# schematic-MAX6675.net
KiCad netlist of a schematic drawn in EAGLE
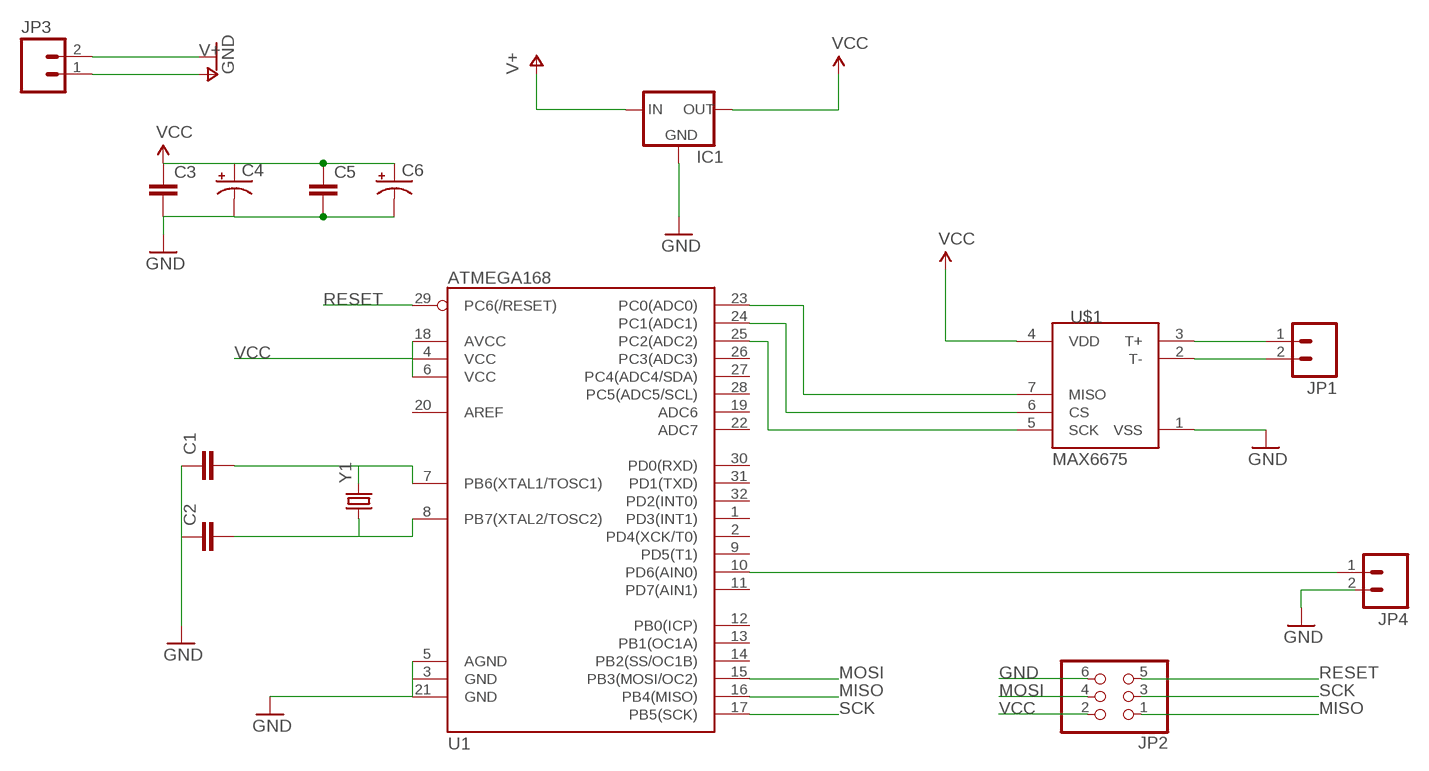
[diagram p0: schematic, sheet 1]

(export (version "E")
  (design (tool "Eeschema 10.0.6"))
  (components
    (comp (ref "C1")
      (value "CAPPTH2")
      (footprint "eagle-import:CAP-PTH-SMALL2")
      (libsource (lib "eagle-import") (part "CAPPTH2"))
    )
    (comp (ref "C2")
      (value "CAPPTH2")
      (footprint "eagle-import:CAP-PTH-SMALL2")
      (libsource (lib "eagle-import") (part "CAPPTH2"))
    )
    (comp (ref "C3")
      (value "CAPPTH")
      (footprint "eagle-import:CAP-PTH-SMALL")
      (libsource (lib "eagle-import") (part "CAPPTH"))
    )
    (comp (ref "C4")
      (value "CAP_POLPTH2")
      (footprint "eagle-import:CPOL-RADIAL-10UF-25V")
      (libsource (lib "eagle-import") (part "CAP_POLPTH2"))
    )
    (comp (ref "C5")
      (value "CAPPTH")
      (footprint "eagle-import:CAP-PTH-SMALL")
      (libsource (lib "eagle-import") (part "CAPPTH"))
    )
    (comp (ref "C6")
      (value "CAP_POLPTH2")
      (footprint "eagle-import:CPOL-RADIAL-10UF-25V")
      (libsource (lib "eagle-import") (part "CAP_POLPTH2"))
    )
    (comp (ref "IC1")
      (value "V_REG_78XXSINK")
      (footprint "eagle-import:TO220-IGO")
      (libsource (lib "eagle-import") (part "V_REG_78XXSINK"))
    )
    (comp (ref "JP1")
      (value "M025MM")
      (footprint "eagle-import:SCREWTERMINAL-5MM-2")
      (libsource (lib "eagle-import") (part "M025MM"))
    )
    (comp (ref "JP2")
      (value "PINHD-2X3")
      (footprint "eagle-import:2X03")
      (libsource (lib "eagle-import") (part "PINHD-2X3"))
    )
    (comp (ref "JP3")
      (value "M023.5MM_LOCK")
      (footprint "eagle-import:SCREWTERMINAL-3.5MM-2_LOCK")
      (libsource (lib "eagle-import") (part "M023.5MM_LOCK"))
    )
    (comp (ref "JP4")
      (value "M023.5MM_LOCK")
      (footprint "eagle-import:SCREWTERMINAL-3.5MM-2_LOCK")
      (libsource (lib "eagle-import") (part "M023.5MM_LOCK"))
    )
    (comp (ref "U$1")
      (value "MAX6675")
      (footprint "eagle-import:SO08-MAX6675")
      (libsource (lib "eagle-import") (part "MAX6675"))
    )
    (comp (ref "U1")
      (value "ATMEGA168")
      (footprint "eagle-import:TQFP32-08")
      (libsource (lib "eagle-import") (part "ATMEGA168"))
    )
    (comp (ref "Y1")
      (value "CRYSTALHC49US")
      (footprint "eagle-import:HC49US")
      (libsource (lib "eagle-import") (part "CRYSTALHC49US"))
    )
  )
  (nets
    (net (code "1") (name "/MISO") (class "Default")
      (node (ref "JP2") (pin "1") (pinfunction "1_1") (pintype "passive"))
      (node (ref "U1") (pin "16") (pinfunction "PB4(MISO)_16") (pintype "bidirectional"))
    )
    (net (code "2") (name "/MOSI") (class "Default")
      (node (ref "JP2") (pin "4") (pinfunction "4_4") (pintype "passive"))
      (node (ref "U1") (pin "15") (pinfunction "PB3(MOSI/OC2)_15") (pintype "bidirectional"))
    )
    (net (code "3") (name "/RESET") (class "Default")
      (node (ref "JP2") (pin "5") (pinfunction "5_5") (pintype "passive"))
      (node (ref "U1") (pin "29") (pinfunction "PC6(/RESET)_29") (pintype "bidirectional"))
    )
    (net (code "4") (name "/SCK") (class "Default")
      (node (ref "JP2") (pin "3") (pinfunction "3_3") (pintype "passive"))
      (node (ref "U1") (pin "17") (pinfunction "PB5(SCK)_17") (pintype "bidirectional"))
    )
    (net (code "5") (name "GND") (class "Default")
      (node (ref "C1") (pin "1") (pinfunction "1_1") (pintype "passive"))
      (node (ref "C2") (pin "1") (pinfunction "1_1") (pintype "passive"))
      (node (ref "C3") (pin "2") (pinfunction "2_2") (pintype "passive"))
      (node (ref "C4") (pin "2") (pinfunction "-_2") (pintype "passive"))
      (node (ref "C5") (pin "2") (pinfunction "2_2") (pintype "passive"))
      (node (ref "C6") (pin "2") (pinfunction "-_2") (pintype "passive"))
      (node (ref "IC1") (pin "GND") (pinfunction "GND_GND") (pintype "input"))
      (node (ref "JP2") (pin "6") (pinfunction "6_6") (pintype "passive"))
      (node (ref "JP3") (pin "2") (pinfunction "2_2") (pintype "passive"))
      (node (ref "U$1") (pin "1") (pinfunction "VSS_1") (pintype "bidirectional"))
      (node (ref "U1") (pin "21") (pinfunction "GND_21") (pintype "bidirectional"))
      (node (ref "U1") (pin "5") (pinfunction "AGND_5") (pintype "bidirectional"))
    )
    (net (code "6") (name "Net-(U$1-CS)") (class "Default")
      (node (ref "U$1") (pin "6") (pinfunction "CS_6") (pintype "bidirectional"))
      (node (ref "U1") (pin "24") (pinfunction "PC1(ADC1)_24") (pintype "bidirectional"))
    )
    (net (code "7") (name "Net-(U$1-MISO)") (class "Default")
      (node (ref "U$1") (pin "7") (pinfunction "MISO_7") (pintype "bidirectional"))
      (node (ref "U1") (pin "23") (pinfunction "PC0(ADC0)_23") (pintype "bidirectional"))
    )
    (net (code "8") (name "Net-(U$1-SCK)") (class "Default")
      (node (ref "U$1") (pin "5") (pinfunction "SCK_5") (pintype "bidirectional"))
      (node (ref "U1") (pin "25") (pinfunction "PC2(ADC2)_25") (pintype "bidirectional"))
    )
    (net (code "9") (name "Net-(U$1-T+)") (class "Default")
      (node (ref "JP1") (pin "1") (pinfunction "1_1") (pintype "passive"))
      (node (ref "U$1") (pin "3") (pinfunction "T+_3") (pintype "bidirectional"))
    )
    (net (code "10") (name "Net-(U$1-T-)") (class "Default")
      (node (ref "JP1") (pin "2") (pinfunction "2_2") (pintype "passive"))
      (node (ref "U$1") (pin "2") (pinfunction "T-_2") (pintype "bidirectional"))
    )
    (net (code "11") (name "Net-(U1-PB6(XTAL1{slash}TOSC1))") (class "Default")
      (node (ref "C1") (pin "2") (pinfunction "2_2") (pintype "passive"))
      (node (ref "U1") (pin "7") (pinfunction "PB6(XTAL1/TOSC1)_7") (pintype "bidirectional"))
      (node (ref "Y1") (pin "2") (pinfunction "2_2") (pintype "passive"))
    )
    (net (code "12") (name "Net-(U1-PB7(XTAL2{slash}TOSC2))") (class "Default")
      (node (ref "C2") (pin "2") (pinfunction "2_2") (pintype "passive"))
      (node (ref "U1") (pin "8") (pinfunction "PB7(XTAL2/TOSC2)_8") (pintype "bidirectional"))
      (node (ref "Y1") (pin "1") (pinfunction "1_1") (pintype "passive"))
    )
    (net (code "13") (name "Net-(U1-PD6(AIN0))") (class "Default")
      (node (ref "JP4") (pin "1") (pinfunction "1_1") (pintype "passive"))
      (node (ref "U1") (pin "10") (pinfunction "PD6(AIN0)_10") (pintype "bidirectional"))
    )
    (net (code "14") (name "V+") (class "Default")
      (node (ref "IC1") (pin "IN") (pinfunction "IN_IN") (pintype "input"))
      (node (ref "JP3") (pin "1") (pinfunction "1_1") (pintype "passive"))
    )
    (net (code "15") (name "VCC") (class "Default")
      (node (ref "C3") (pin "1") (pinfunction "1_1") (pintype "passive"))
      (node (ref "C4") (pin "1") (pinfunction "+_1") (pintype "passive"))
      (node (ref "C5") (pin "1") (pinfunction "1_1") (pintype "passive"))
      (node (ref "C6") (pin "1") (pinfunction "+_1") (pintype "passive"))
      (node (ref "IC1") (pin "OUT") (pinfunction "OUT_OUT") (pintype "output"))
      (node (ref "JP2") (pin "2") (pinfunction "2_2") (pintype "passive"))
      (node (ref "U$1") (pin "4") (pinfunction "VDD_4") (pintype "bidirectional"))
      (node (ref "U1") (pin "18") (pinfunction "AVCC_18") (pintype "bidirectional"))
      (node (ref "U1") (pin "4") (pinfunction "VCC_4") (pintype "bidirectional"))
      (node (ref "U1") (pin "6") (pinfunction "VCC_6") (pintype "bidirectional"))
    )
    (net (code "16") (name "unconnected-(JP4-Pad2)") (class "Default")
      (node (ref "JP4") (pin "2") (pinfunction "2_2") (pintype "passive"))
    )
    (net (code "17") (name "unconnected-(U1-ADC6-Pad19)") (class "Default")
      (node (ref "U1") (pin "19") (pinfunction "ADC6_19") (pintype "bidirectional"))
    )
    (net (code "18") (name "unconnected-(U1-ADC7-Pad22)") (class "Default")
      (node (ref "U1") (pin "22") (pinfunction "ADC7_22") (pintype "bidirectional"))
    )
    (net (code "19") (name "unconnected-(U1-AREF-Pad20)") (class "Default")
      (node (ref "U1") (pin "20") (pinfunction "AREF_20") (pintype "bidirectional"))
    )
    (net (code "20") (name "unconnected-(U1-GND-Pad3)") (class "Default")
      (node (ref "U1") (pin "3") (pinfunction "GND_3") (pintype "bidirectional"))
    )
    (net (code "21") (name "unconnected-(U1-PB0(ICP)-Pad12)") (class "Default")
      (node (ref "U1") (pin "12") (pinfunction "PB0(ICP)_12") (pintype "bidirectional"))
    )
    (net (code "22") (name "unconnected-(U1-PB1(OC1A)-Pad13)") (class "Default")
      (node (ref "U1") (pin "13") (pinfunction "PB1(OC1A)_13") (pintype "bidirectional"))
    )
    (net (code "23") (name "unconnected-(U1-PB2(SS{slash}OC1B)-Pad14)") (class "Default")
      (node (ref "U1") (pin "14") (pinfunction "PB2(SS/OC1B)_14") (pintype "bidirectional"))
    )
    (net (code "24") (name "unconnected-(U1-PC3(ADC3)-Pad26)") (class "Default")
      (node (ref "U1") (pin "26") (pinfunction "PC3(ADC3)_26") (pintype "bidirectional"))
    )
    (net (code "25") (name "unconnected-(U1-PC4(ADC4{slash}SDA)-Pad27)") (class "Default")
      (node (ref "U1") (pin "27") (pinfunction "PC4(ADC4/SDA)_27") (pintype "bidirectional"))
    )
    (net (code "26") (name "unconnected-(U1-PC5(ADC5{slash}SCL)-Pad28)") (class "Default")
      (node (ref "U1") (pin "28") (pinfunction "PC5(ADC5/SCL)_28") (pintype "bidirectional"))
    )
    (net (code "27") (name "unconnected-(U1-PD0(RXD)-Pad30)") (class "Default")
      (node (ref "U1") (pin "30") (pinfunction "PD0(RXD)_30") (pintype "bidirectional"))
    )
    (net (code "28") (name "unconnected-(U1-PD1(TXD)-Pad31)") (class "Default")
      (node (ref "U1") (pin "31") (pinfunction "PD1(TXD)_31") (pintype "bidirectional"))
    )
    (net (code "29") (name "unconnected-(U1-PD2(INT0)-Pad32)") (class "Default")
      (node (ref "U1") (pin "32") (pinfunction "PD2(INT0)_32") (pintype "bidirectional"))
    )
    (net (code "30") (name "unconnected-(U1-PD3(INT1)-Pad1)") (class "Default")
      (node (ref "U1") (pin "1") (pinfunction "PD3(INT1)_1") (pintype "bidirectional"))
    )
    (net (code "31") (name "unconnected-(U1-PD4(XCK{slash}T0)-Pad2)") (class "Default")
      (node (ref "U1") (pin "2") (pinfunction "PD4(XCK/T0)_2") (pintype "bidirectional"))
    )
    (net (code "32") (name "unconnected-(U1-PD5(T1)-Pad9)") (class "Default")
      (node (ref "U1") (pin "9") (pinfunction "PD5(T1)_9") (pintype "bidirectional"))
    )
    (net (code "33") (name "unconnected-(U1-PD7(AIN1)-Pad11)") (class "Default")
      (node (ref "U1") (pin "11") (pinfunction "PD7(AIN1)_11") (pintype "bidirectional"))
    )
  )
)
